# design.net
KiCad netlist of a schematic drawn in Altium Designer
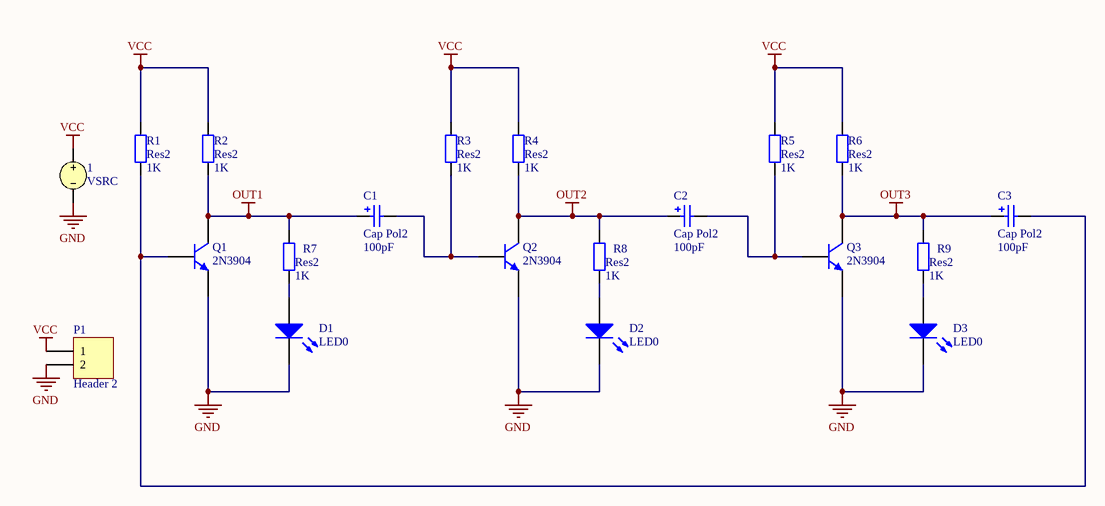
[diagram p0: 跑马灯.SchDoc]

(export (version "E")
  (design (tool "Eeschema 10.0.6"))
  (components
    (comp (ref "1")
      (value "VSRC")
      (description "Voltage Source")
      (fields (field (name "PUBLISHER") "Altium Limited"))
      (libsource (lib "Simulation Sources") (part "VSRC"))
    )
    (comp (ref "C1")
      (value "Cap Pol2")
      (footprint "POLAR0.8")
      (description "Polarized Capacitor (Axial)")
      (fields (field (name "ALTIUM_VALUE") "100pF") (field (name "PUBLISHER") "Altium Limited"))
      (libsource (lib "Miscellaneous Devices") (part "Cap Pol2"))
    )
    (comp (ref "C2")
      (value "Cap Pol2")
      (footprint "POLAR0.8")
      (description "Polarized Capacitor (Axial)")
      (fields (field (name "ALTIUM_VALUE") "100pF") (field (name "PUBLISHER") "Altium Limited"))
      (libsource (lib "Miscellaneous Devices") (part "Cap Pol2"))
    )
    (comp (ref "C3")
      (value "Cap Pol2")
      (footprint "POLAR0.8")
      (description "Polarized Capacitor (Axial)")
      (fields (field (name "ALTIUM_VALUE") "100pF") (field (name "PUBLISHER") "Altium Limited"))
      (libsource (lib "Miscellaneous Devices") (part "Cap Pol2"))
    )
    (comp (ref "D1")
      (value "LED0")
      (footprint "LED-0")
      (description "Typical INFRARED GaAs LED")
      (fields (field (name "PUBLISHER") "Altium Limited"))
      (libsource (lib "Miscellaneous Devices") (part "LED0"))
    )
    (comp (ref "D2")
      (value "LED0")
      (footprint "LED-0")
      (description "Typical INFRARED GaAs LED")
      (fields (field (name "PUBLISHER") "Altium Limited"))
      (libsource (lib "Miscellaneous Devices") (part "LED0"))
    )
    (comp (ref "D3")
      (value "LED0")
      (footprint "LED-0")
      (description "Typical INFRARED GaAs LED")
      (fields (field (name "PUBLISHER") "Altium Limited"))
      (libsource (lib "Miscellaneous Devices") (part "LED0"))
    )
    (comp (ref "P1")
      (value "Header 2")
      (footprint "HDR1X2")
      (description "Header, 2-Pin")
      (fields (field (name "PUBLISHER") "Altium Limited"))
      (libsource (lib "Miscellaneous Connectors") (part "Header 2"))
    )
    (comp (ref "Q1")
      (value "2N3904")
      (footprint "TO-92A")
      (description "NPN General Purpose Amplifier")
      (fields (field (name "PUBLISHER") "Altium Limited"))
      (libsource (lib "Miscellaneous Devices") (part "2N3904"))
    )
    (comp (ref "Q2")
      (value "2N3904")
      (footprint "TO-92A")
      (description "NPN General Purpose Amplifier")
      (fields (field (name "PUBLISHER") "Altium Limited"))
      (libsource (lib "Miscellaneous Devices") (part "2N3904"))
    )
    (comp (ref "Q3")
      (value "2N3904")
      (footprint "TO-92A")
      (description "NPN General Purpose Amplifier")
      (fields (field (name "PUBLISHER") "Altium Limited"))
      (libsource (lib "Miscellaneous Devices") (part "2N3904"))
    )
    (comp (ref "R1")
      (value "Res2")
      (footprint "AXIAL-0.4")
      (description "Resistor")
      (fields (field (name "ALTIUM_VALUE") "1K") (field (name "PUBLISHER") "Altium Limited"))
      (libsource (lib "Miscellaneous Devices") (part "Res2"))
    )
    (comp (ref "R2")
      (value "Res2")
      (footprint "AXIAL-0.4")
      (description "Resistor")
      (fields (field (name "ALTIUM_VALUE") "1K") (field (name "PUBLISHER") "Altium Limited"))
      (libsource (lib "Miscellaneous Devices") (part "Res2"))
    )
    (comp (ref "R3")
      (value "Res2")
      (footprint "AXIAL-0.4")
      (description "Resistor")
      (fields (field (name "ALTIUM_VALUE") "1K") (field (name "PUBLISHER") "Altium Limited"))
      (libsource (lib "Miscellaneous Devices") (part "Res2"))
    )
    (comp (ref "R4")
      (value "Res2")
      (footprint "AXIAL-0.4")
      (description "Resistor")
      (fields (field (name "ALTIUM_VALUE") "1K") (field (name "PUBLISHER") "Altium Limited"))
      (libsource (lib "Miscellaneous Devices") (part "Res2"))
    )
    (comp (ref "R5")
      (value "Res2")
      (footprint "AXIAL-0.4")
      (description "Resistor")
      (fields (field (name "ALTIUM_VALUE") "1K") (field (name "PUBLISHER") "Altium Limited"))
      (libsource (lib "Miscellaneous Devices") (part "Res2"))
    )
    (comp (ref "R6")
      (value "Res2")
      (footprint "AXIAL-0.4")
      (description "Resistor")
      (fields (field (name "ALTIUM_VALUE") "1K") (field (name "PUBLISHER") "Altium Limited"))
      (libsource (lib "Miscellaneous Devices") (part "Res2"))
    )
    (comp (ref "R7")
      (value "Res2")
      (footprint "AXIAL-0.4")
      (description "Resistor")
      (fields (field (name "ALTIUM_VALUE") "1K") (field (name "PUBLISHER") "Altium Limited"))
      (libsource (lib "Miscellaneous Devices") (part "Res2"))
    )
    (comp (ref "R8")
      (value "Res2")
      (footprint "AXIAL-0.4")
      (description "Resistor")
      (fields (field (name "ALTIUM_VALUE") "1K") (field (name "PUBLISHER") "Altium Limited"))
      (libsource (lib "Miscellaneous Devices") (part "Res2"))
    )
    (comp (ref "R9")
      (value "Res2")
      (footprint "AXIAL-0.4")
      (description "Resistor")
      (fields (field (name "ALTIUM_VALUE") "1K") (field (name "PUBLISHER") "Altium Limited"))
      (libsource (lib "Miscellaneous Devices") (part "Res2"))
    )
  )
  (nets
    (net (code "1") (name "GND") (class "Default")
      (node (ref "1") (pin "2") (pinfunction "2_2") (pintype "passive"))
      (node (ref "D1") (pin "2") (pinfunction "K_2") (pintype "passive"))
      (node (ref "D2") (pin "2") (pinfunction "K_2") (pintype "passive"))
      (node (ref "D3") (pin "2") (pinfunction "K_2") (pintype "passive"))
      (node (ref "P1") (pin "2") (pinfunction "2_2") (pintype "passive"))
      (node (ref "Q1") (pin "1") (pinfunction "E_1") (pintype "passive"))
      (node (ref "Q2") (pin "1") (pinfunction "E_1") (pintype "passive"))
      (node (ref "Q3") (pin "1") (pinfunction "E_1") (pintype "passive"))
    )
    (net (code "2") (name "Net-(D1-A)") (class "Default")
      (node (ref "D1") (pin "1") (pinfunction "A_1") (pintype "passive"))
      (node (ref "R7") (pin "2") (pinfunction "2_2") (pintype "passive"))
    )
    (net (code "3") (name "Net-(D2-A)") (class "Default")
      (node (ref "D2") (pin "1") (pinfunction "A_1") (pintype "passive"))
      (node (ref "R8") (pin "2") (pinfunction "2_2") (pintype "passive"))
    )
    (net (code "4") (name "Net-(D3-A)") (class "Default")
      (node (ref "D3") (pin "1") (pinfunction "A_1") (pintype "passive"))
      (node (ref "R9") (pin "2") (pinfunction "2_2") (pintype "passive"))
    )
    (net (code "5") (name "Net-(Q1-B)") (class "Default")
      (node (ref "C3") (pin "2") (pinfunction "2_2") (pintype "passive"))
      (node (ref "Q1") (pin "2") (pinfunction "B_2") (pintype "passive"))
      (node (ref "R1") (pin "2") (pinfunction "2_2") (pintype "passive"))
    )
    (net (code "6") (name "Net-(Q2-B)") (class "Default")
      (node (ref "C1") (pin "2") (pinfunction "2_2") (pintype "passive"))
      (node (ref "Q2") (pin "2") (pinfunction "B_2") (pintype "passive"))
      (node (ref "R3") (pin "2") (pinfunction "2_2") (pintype "passive"))
    )
    (net (code "7") (name "Net-(Q3-B)") (class "Default")
      (node (ref "C2") (pin "2") (pinfunction "2_2") (pintype "passive"))
      (node (ref "Q3") (pin "2") (pinfunction "B_2") (pintype "passive"))
      (node (ref "R5") (pin "2") (pinfunction "2_2") (pintype "passive"))
    )
    (net (code "8") (name "OUT1") (class "Default")
      (node (ref "C1") (pin "1") (pinfunction "1_1") (pintype "passive"))
      (node (ref "Q1") (pin "3") (pinfunction "C_3") (pintype "passive"))
      (node (ref "R2") (pin "2") (pinfunction "2_2") (pintype "passive"))
      (node (ref "R7") (pin "1") (pinfunction "1_1") (pintype "passive"))
    )
    (net (code "9") (name "OUT2") (class "Default")
      (node (ref "C2") (pin "1") (pinfunction "1_1") (pintype "passive"))
      (node (ref "Q2") (pin "3") (pinfunction "C_3") (pintype "passive"))
      (node (ref "R4") (pin "2") (pinfunction "2_2") (pintype "passive"))
      (node (ref "R8") (pin "1") (pinfunction "1_1") (pintype "passive"))
    )
    (net (code "10") (name "OUT3") (class "Default")
      (node (ref "C3") (pin "1") (pinfunction "1_1") (pintype "passive"))
      (node (ref "Q3") (pin "3") (pinfunction "C_3") (pintype "passive"))
      (node (ref "R6") (pin "2") (pinfunction "2_2") (pintype "passive"))
      (node (ref "R9") (pin "1") (pinfunction "1_1") (pintype "passive"))
    )
    (net (code "11") (name "VCC") (class "Default")
      (node (ref "1") (pin "1") (pinfunction "1_1") (pintype "passive"))
      (node (ref "P1") (pin "1") (pinfunction "1_1") (pintype "passive"))
      (node (ref "R1") (pin "1") (pinfunction "1_1") (pintype "passive"))
      (node (ref "R2") (pin "1") (pinfunction "1_1") (pintype "passive"))
      (node (ref "R3") (pin "1") (pinfunction "1_1") (pintype "passive"))
      (node (ref "R4") (pin "1") (pinfunction "1_1") (pintype "passive"))
      (node (ref "R5") (pin "1") (pinfunction "1_1") (pintype "passive"))
      (node (ref "R6") (pin "1") (pinfunction "1_1") (pintype "passive"))
    )
  )
)
